# CanSplitter.net
KiCad netlist of a schematic drawn in EAGLE
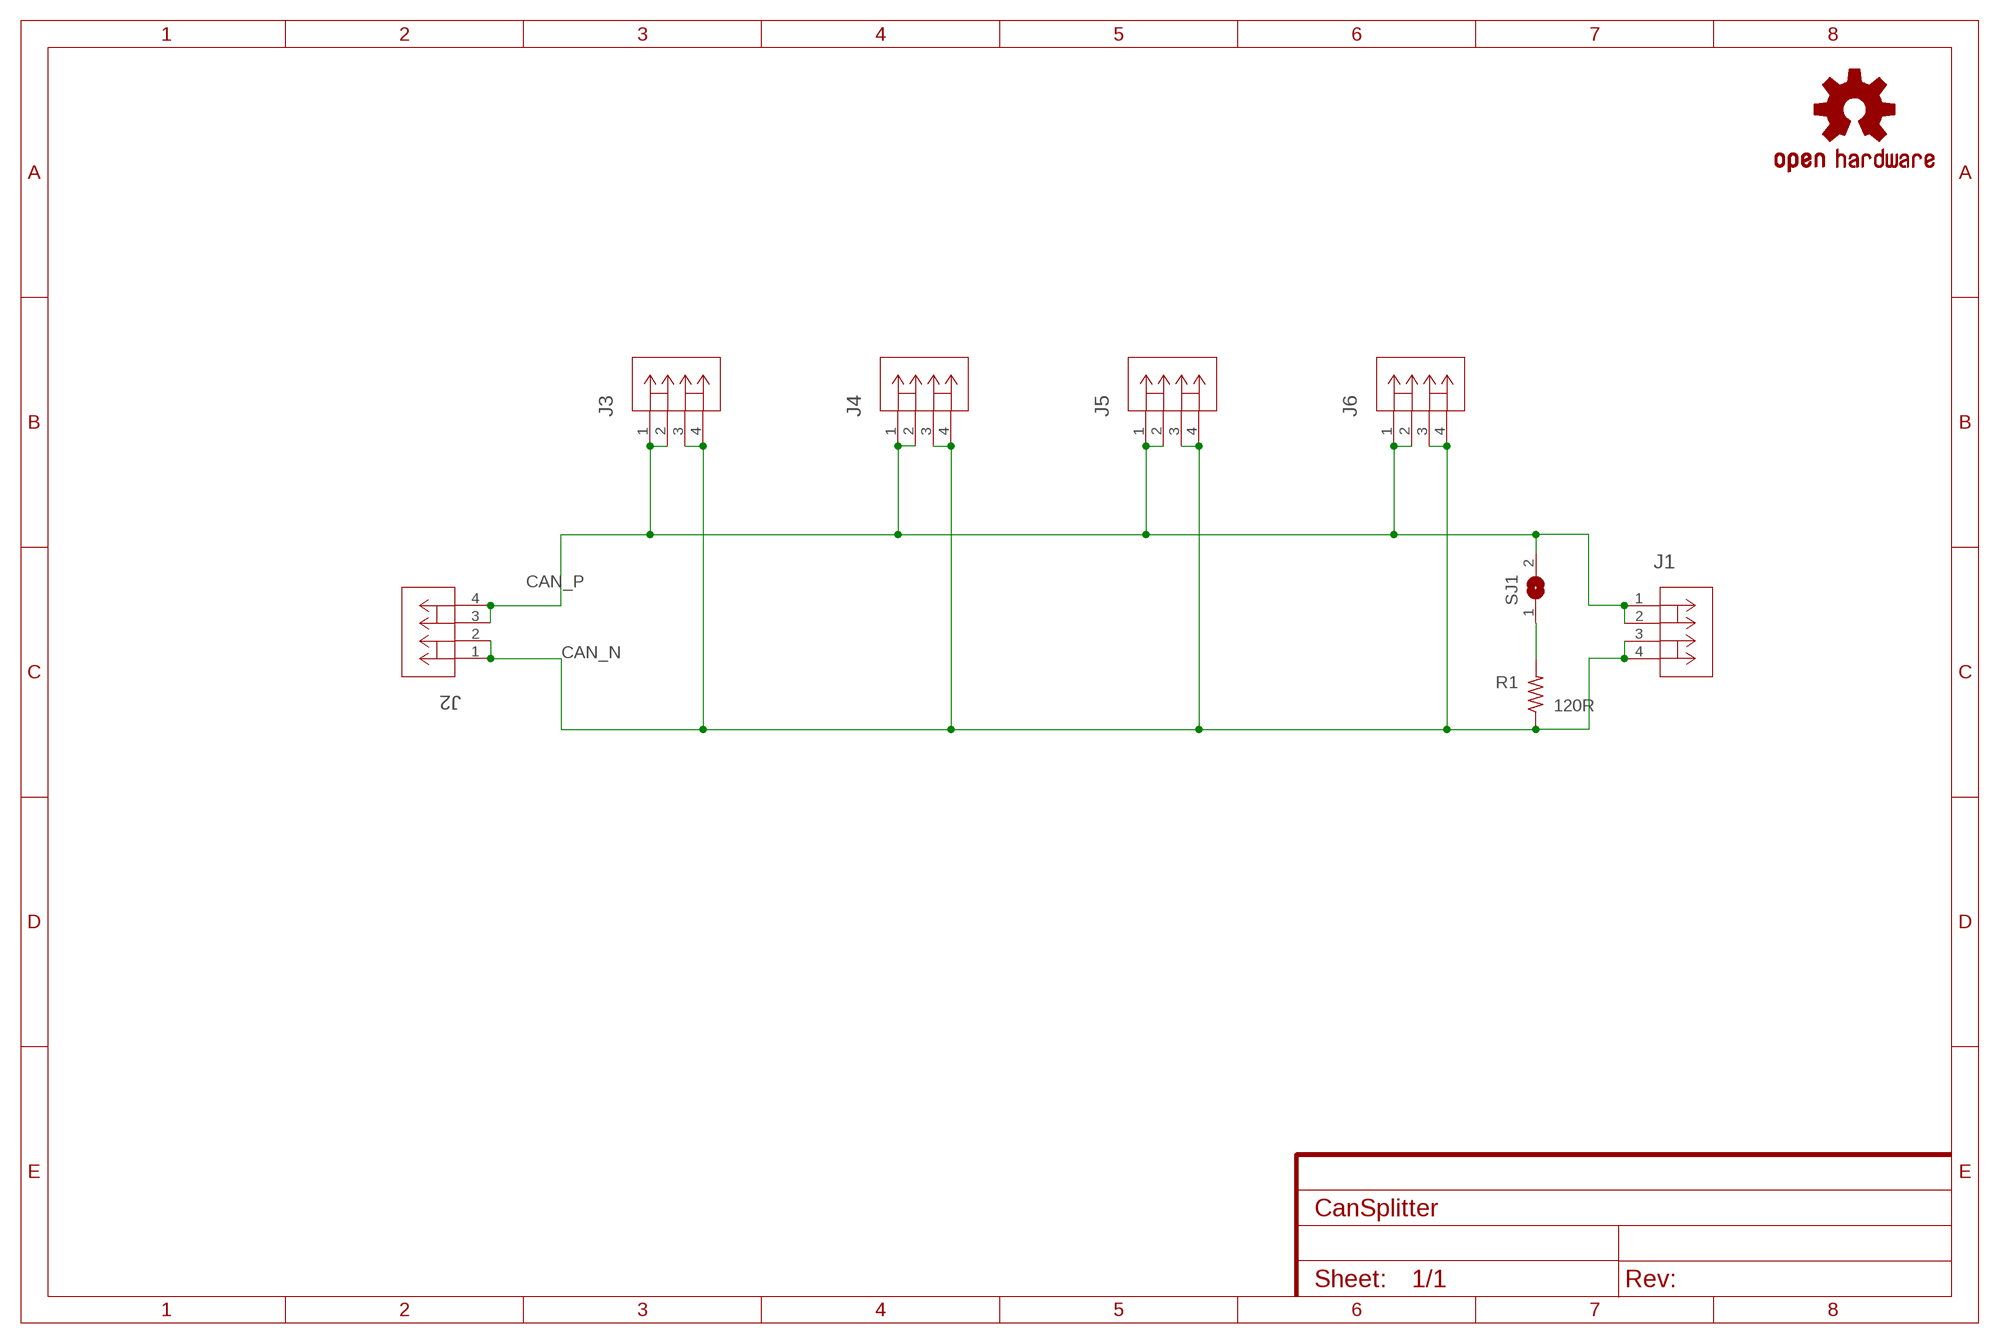
[diagram p0: schematic, sheet 1]

(export (version "E")
  (design (tool "Eeschema 10.0.6"))
  (components
    (comp (ref "J1")
      (value "1885650000")
      (footprint "eagle-import:CONN4_1885650000_WED")
      (fields (field (name "COPYRIGHT") "Copyright (C) 2025 Ultra Librarian. All rights reserved."))
      (libsource (lib "eagle-import") (part "1885650000"))
    )
    (comp (ref "J2")
      (value "1885650000")
      (footprint "eagle-import:CONN4_1885650000_WED")
      (fields (field (name "COPYRIGHT") "Copyright (C) 2025 Ultra Librarian. All rights reserved."))
      (libsource (lib "eagle-import") (part "1885650000"))
    )
    (comp (ref "J3")
      (value "1885650000")
      (footprint "eagle-import:CONN4_1885650000_WED")
      (fields (field (name "COPYRIGHT") "Copyright (C) 2025 Ultra Librarian. All rights reserved."))
      (libsource (lib "eagle-import") (part "1885650000"))
    )
    (comp (ref "J4")
      (value "1885650000")
      (footprint "eagle-import:CONN4_1885650000_WED")
      (fields (field (name "COPYRIGHT") "Copyright (C) 2025 Ultra Librarian. All rights reserved."))
      (libsource (lib "eagle-import") (part "1885650000"))
    )
    (comp (ref "J5")
      (value "1885650000")
      (footprint "eagle-import:CONN4_1885650000_WED")
      (fields (field (name "COPYRIGHT") "Copyright (C) 2025 Ultra Librarian. All rights reserved."))
      (libsource (lib "eagle-import") (part "1885650000"))
    )
    (comp (ref "J6")
      (value "1885650000")
      (footprint "eagle-import:CONN4_1885650000_WED")
      (fields (field (name "COPYRIGHT") "Copyright (C) 2025 Ultra Librarian. All rights reserved."))
      (libsource (lib "eagle-import") (part "1885650000"))
    )
    (comp (ref "LOGO1")
      (value "OSHW-LOGOL")
      (footprint "eagle-import:OSHW-LOGO-L")
      (libsource (lib "eagle-import") (part "OSHW-LOGOL"))
    )
    (comp (ref "R1")
      (value "120R")
      (footprint "eagle-import:R0603")
      (libsource (lib "eagle-import") (part "R-US_R0603"))
    )
    (comp (ref "SJ1") (value "SJ") (footprint "eagle-import:SJ") (libsource (lib "eagle-import") (part "SJ")))
  )
  (nets
    (net (code "1") (name "/CAN_N") (class "Default")
      (node (ref "J1") (pin "3") (pinfunction "3_3") (pintype "passive"))
      (node (ref "J1") (pin "4") (pinfunction "4_4") (pintype "passive"))
      (node (ref "J2") (pin "1") (pinfunction "1_1") (pintype "passive"))
      (node (ref "J2") (pin "2") (pinfunction "2_2") (pintype "passive"))
      (node (ref "J3") (pin "3") (pinfunction "3_3") (pintype "passive"))
      (node (ref "J3") (pin "4") (pinfunction "4_4") (pintype "passive"))
      (node (ref "J4") (pin "3") (pinfunction "3_3") (pintype "passive"))
      (node (ref "J4") (pin "4") (pinfunction "4_4") (pintype "passive"))
      (node (ref "J5") (pin "3") (pinfunction "3_3") (pintype "passive"))
      (node (ref "J5") (pin "4") (pinfunction "4_4") (pintype "passive"))
      (node (ref "J6") (pin "3") (pinfunction "3_3") (pintype "passive"))
      (node (ref "J6") (pin "4") (pinfunction "4_4") (pintype "passive"))
      (node (ref "R1") (pin "1") (pinfunction "1_1") (pintype "passive"))
    )
    (net (code "2") (name "/CAN_P") (class "Default")
      (node (ref "J1") (pin "1") (pinfunction "1_1") (pintype "passive"))
      (node (ref "J1") (pin "2") (pinfunction "2_2") (pintype "passive"))
      (node (ref "J2") (pin "3") (pinfunction "3_3") (pintype "passive"))
      (node (ref "J2") (pin "4") (pinfunction "4_4") (pintype "passive"))
      (node (ref "J3") (pin "1") (pinfunction "1_1") (pintype "passive"))
      (node (ref "J3") (pin "2") (pinfunction "2_2") (pintype "passive"))
      (node (ref "J4") (pin "1") (pinfunction "1_1") (pintype "passive"))
      (node (ref "J4") (pin "2") (pinfunction "2_2") (pintype "passive"))
      (node (ref "J5") (pin "1") (pinfunction "1_1") (pintype "passive"))
      (node (ref "J5") (pin "2") (pinfunction "2_2") (pintype "passive"))
      (node (ref "J6") (pin "1") (pinfunction "1_1") (pintype "passive"))
      (node (ref "J6") (pin "2") (pinfunction "2_2") (pintype "passive"))
      (node (ref "SJ1") (pin "2") (pinfunction "2_2") (pintype "passive"))
    )
    (net (code "3") (name "Net-(R1-Pad2)") (class "Default")
      (node (ref "R1") (pin "2") (pinfunction "2_2") (pintype "passive"))
      (node (ref "SJ1") (pin "1") (pinfunction "1_1") (pintype "passive"))
    )
  )
)
